# m1-output-reg.net
KiCad netlist of a schematic drawn in EAGLE
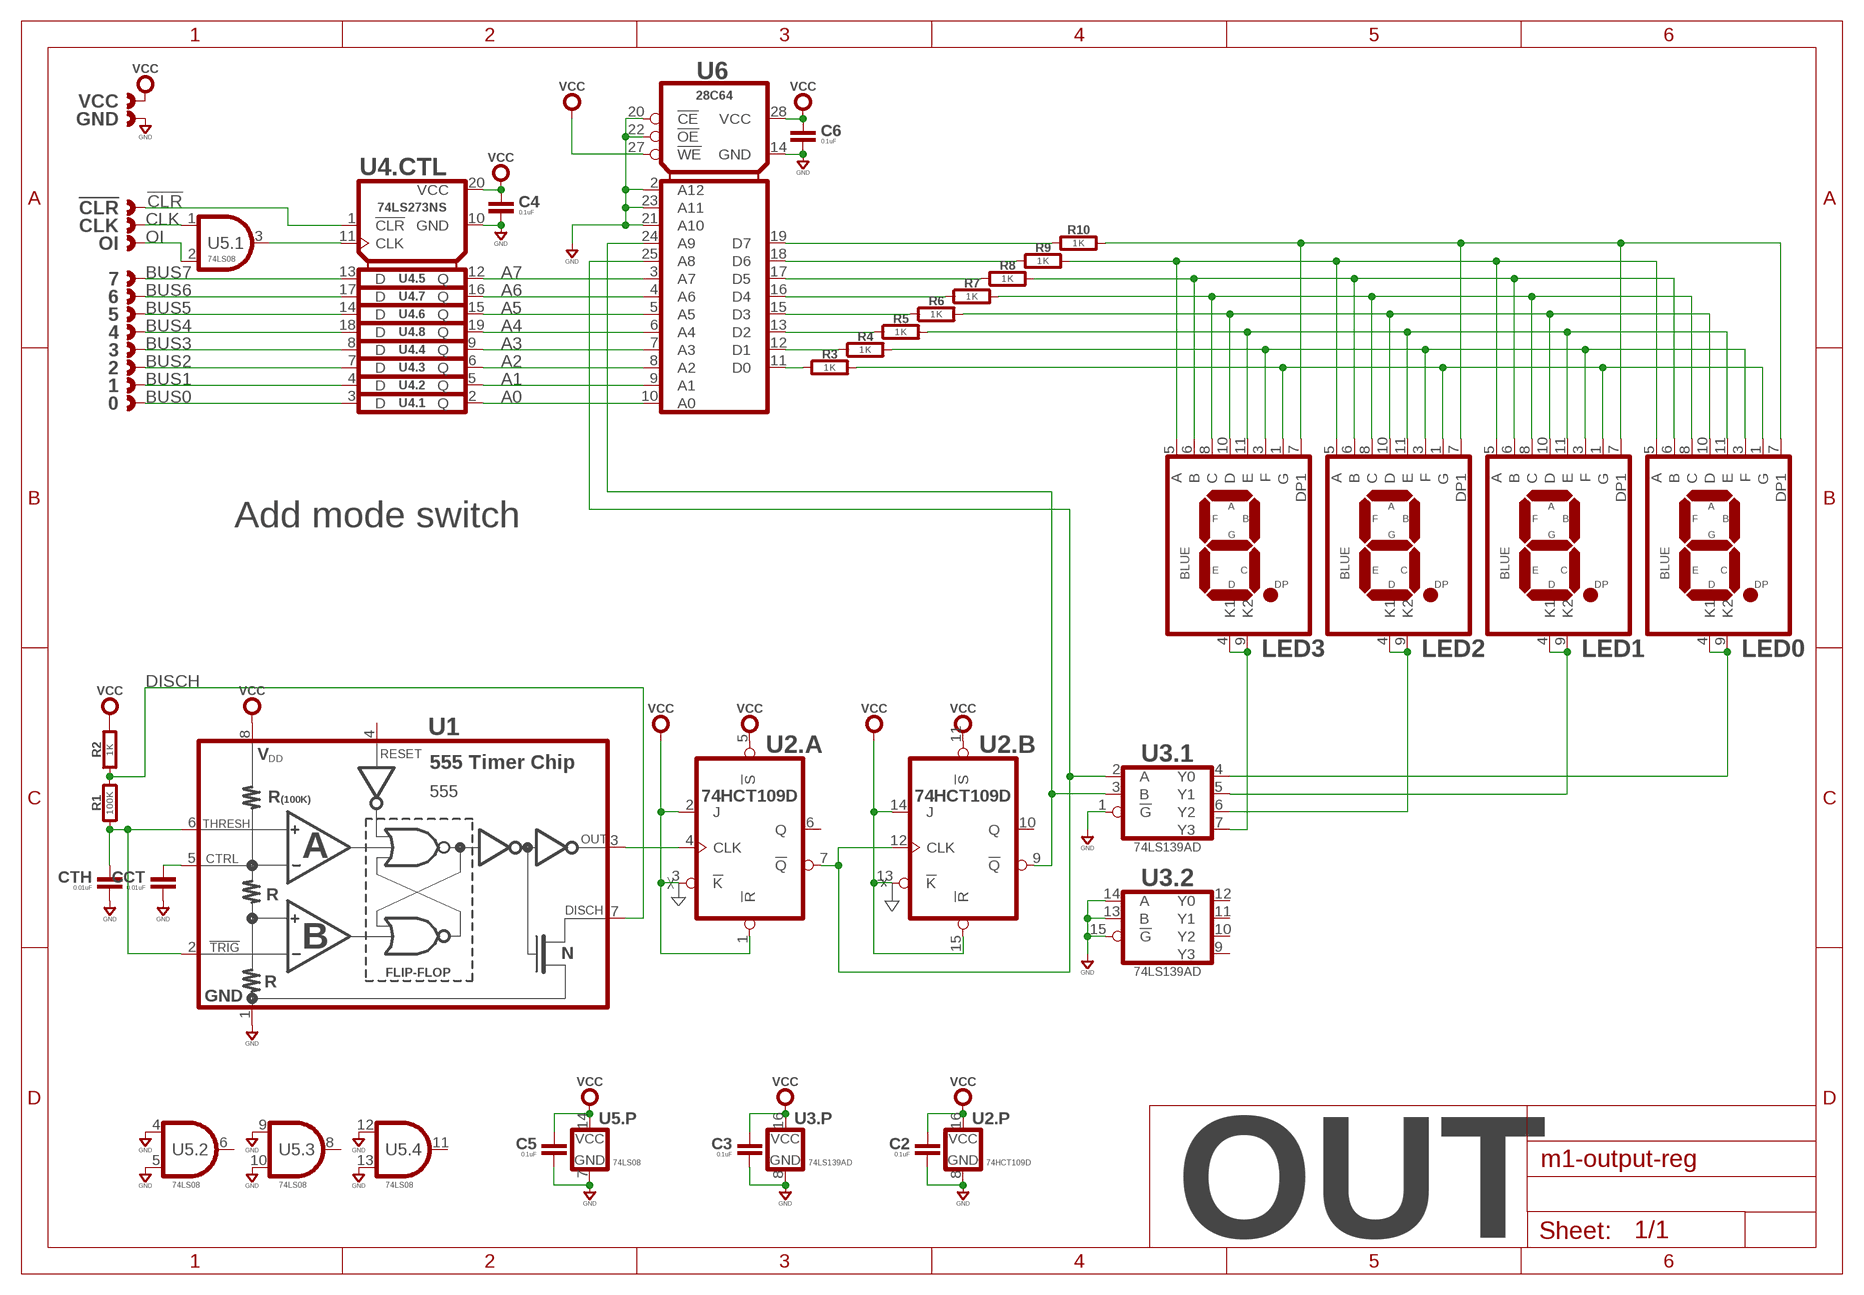
[diagram p0: schematic, sheet 1]

(export (version "E")
  (design (tool "Eeschema 10.0.6"))
  (components
    (comp (ref "!CLR")
      (value "CAST-01X1")
      (footprint "eagle-import:CAST01-2.54MM")
      (libsource (lib "eagle-import") (part "CAST-01X1"))
    )
    (comp (ref "0")
      (value "CAST-01X1")
      (footprint "eagle-import:CAST01-2.54MM")
      (libsource (lib "eagle-import") (part "CAST-01X1"))
    )
    (comp (ref "1")
      (value "CAST-01X1")
      (footprint "eagle-import:CAST01-2.54MM")
      (libsource (lib "eagle-import") (part "CAST-01X1"))
    )
    (comp (ref "2")
      (value "CAST-01X1")
      (footprint "eagle-import:CAST01-2.54MM")
      (libsource (lib "eagle-import") (part "CAST-01X1"))
    )
    (comp (ref "3")
      (value "CAST-01X1")
      (footprint "eagle-import:CAST01-2.54MM")
      (libsource (lib "eagle-import") (part "CAST-01X1"))
    )
    (comp (ref "4")
      (value "CAST-01X1")
      (footprint "eagle-import:CAST01-2.54MM")
      (libsource (lib "eagle-import") (part "CAST-01X1"))
    )
    (comp (ref "5")
      (value "CAST-01X1")
      (footprint "eagle-import:CAST01-2.54MM")
      (libsource (lib "eagle-import") (part "CAST-01X1"))
    )
    (comp (ref "6")
      (value "CAST-01X1")
      (footprint "eagle-import:CAST01-2.54MM")
      (libsource (lib "eagle-import") (part "CAST-01X1"))
    )
    (comp (ref "7")
      (value "CAST-01X1")
      (footprint "eagle-import:CAST01-2.54MM")
      (libsource (lib "eagle-import") (part "CAST-01X1"))
    )
    (comp (ref "C2")
      (value "0.1uF")
      (footprint "eagle-import:0603-CAP")
      (libsource (lib "eagle-import") (part "CAPACITOR0603"))
    )
    (comp (ref "C3")
      (value "0.1uF")
      (footprint "eagle-import:0603-CAP")
      (libsource (lib "eagle-import") (part "CAPACITOR0603"))
    )
    (comp (ref "C4")
      (value "0.1uF")
      (footprint "eagle-import:0603-CAP")
      (libsource (lib "eagle-import") (part "CAPACITOR0603"))
    )
    (comp (ref "C5")
      (value "0.1uF")
      (footprint "eagle-import:0603-CAP")
      (libsource (lib "eagle-import") (part "CAPACITOR0603"))
    )
    (comp (ref "C6")
      (value "0.1uF")
      (footprint "eagle-import:0603-CAP")
      (libsource (lib "eagle-import") (part "CAPACITOR0603"))
    )
    (comp (ref "CCT")
      (value "0.01uF")
      (footprint "eagle-import:0603-CAP")
      (libsource (lib "eagle-import") (part "CAPACITOR0603"))
    )
    (comp (ref "CLK")
      (value "CAST-01X1")
      (footprint "eagle-import:CAST01-2.54MM")
      (libsource (lib "eagle-import") (part "CAST-01X1"))
    )
    (comp (ref "CTH")
      (value "0.01uF")
      (footprint "eagle-import:0603-CAP")
      (libsource (lib "eagle-import") (part "CAPACITOR0603"))
    )
    (comp (ref "GND")
      (value "CAST-01X1")
      (footprint "eagle-import:CAST01-2.54MM")
      (libsource (lib "eagle-import") (part "CAST-01X1"))
    )
    (comp (ref "LED0")
      (value "BLUE")
      (footprint "eagle-import:AVAGO-HDSM-281B-7SEG")
      (fields (field (name "MFR") "Avago") (field (name "MPN") "HDSM-283B"))
      (libsource (lib "eagle-import") (part "SEVEN_SEG_DISP_DP028-BLUE"))
    )
    (comp (ref "LED1")
      (value "BLUE")
      (footprint "eagle-import:AVAGO-HDSM-281B-7SEG")
      (fields (field (name "MFR") "Avago") (field (name "MPN") "HDSM-283B"))
      (libsource (lib "eagle-import") (part "SEVEN_SEG_DISP_DP028-BLUE"))
    )
    (comp (ref "LED2")
      (value "BLUE")
      (footprint "eagle-import:AVAGO-HDSM-281B-7SEG")
      (fields (field (name "MFR") "Avago") (field (name "MPN") "HDSM-283B"))
      (libsource (lib "eagle-import") (part "SEVEN_SEG_DISP_DP028-BLUE"))
    )
    (comp (ref "LED3")
      (value "BLUE")
      (footprint "eagle-import:AVAGO-HDSM-281B-7SEG")
      (fields (field (name "MFR") "Avago") (field (name "MPN") "HDSM-283B"))
      (libsource (lib "eagle-import") (part "SEVEN_SEG_DISP_DP028-BLUE"))
    )
    (comp (ref "OI")
      (value "CAST-01X1")
      (footprint "eagle-import:CAST01-2.54MM")
      (libsource (lib "eagle-import") (part "CAST-01X1"))
    )
    (comp (ref "R1")
      (value "100K")
      (footprint "eagle-import:0603-RES")
      (libsource (lib "eagle-import") (part "RESISTOR0603"))
    )
    (comp (ref "R2")
      (value "1K")
      (footprint "eagle-import:0603-RES")
      (libsource (lib "eagle-import") (part "RESISTOR0603"))
    )
    (comp (ref "R3")
      (value "1K")
      (footprint "eagle-import:0603-RES")
      (libsource (lib "eagle-import") (part "RESISTOR0603"))
    )
    (comp (ref "R4")
      (value "1K")
      (footprint "eagle-import:0603-RES")
      (libsource (lib "eagle-import") (part "RESISTOR0603"))
    )
    (comp (ref "R5")
      (value "1K")
      (footprint "eagle-import:0603-RES")
      (libsource (lib "eagle-import") (part "RESISTOR0603"))
    )
    (comp (ref "R6")
      (value "1K")
      (footprint "eagle-import:0603-RES")
      (libsource (lib "eagle-import") (part "RESISTOR0603"))
    )
    (comp (ref "R7")
      (value "1K")
      (footprint "eagle-import:0603-RES")
      (libsource (lib "eagle-import") (part "RESISTOR0603"))
    )
    (comp (ref "R8")
      (value "1K")
      (footprint "eagle-import:0603-RES")
      (libsource (lib "eagle-import") (part "RESISTOR0603"))
    )
    (comp (ref "R9")
      (value "1K")
      (footprint "eagle-import:0603-RES")
      (libsource (lib "eagle-import") (part "RESISTOR0603"))
    )
    (comp (ref "R10")
      (value "1K")
      (footprint "eagle-import:0603-RES")
      (libsource (lib "eagle-import") (part "RESISTOR0603"))
    )
    (comp (ref "U1")
      (value "555")
      (footprint "eagle-import:SOP08")
      (fields (field (name "MFR") "TI") (field (name "MPN") "NE555PSR"))
      (libsource (lib "eagle-import") (part "555SOIC"))
    )
    (comp (ref "U2")
      (value "74HCT109D")
      (footprint "eagle-import:SO16")
      (libsource (lib "eagle-import") (part "74109?DAHCT"))
    )
    (comp (ref "U3")
      (value "74LS139AD")
      (footprint "eagle-import:SO16")
      (libsource (lib "eagle-import") (part "74139?DLS"))
    )
    (comp (ref "U4")
      (value "74LS273NS")
      (footprint "eagle-import:SO20")
      (libsource (lib "eagle-import") (part "74273?NSLS"))
    )
    (comp (ref "U5")
      (value "74LS08")
      (footprint "eagle-import:SOP14")
      (fields (field (name "MPN") "74LS08D"))
      (libsource (lib "eagle-import") (part "7408?DLS"))
    )
    (comp (ref "U6")
      (value "28C64")
      (footprint "eagle-import:SO28")
      (fields (field (name "MFR") "Microchip") (field (name "MPN") "AT28C64B-15SU"))
      (libsource (lib "eagle-import") (part "2864?SC"))
    )
    (comp (ref "VCC")
      (value "CAST-01X1")
      (footprint "eagle-import:CAST01-2.54MM")
      (libsource (lib "eagle-import") (part "CAST-01X1"))
    )
  )
  (nets
    (net (code "1") (name "/A0") (class "Default")
      (node (ref "U4") (pin "2") (pinfunction "Q_2") (pintype "output"))
      (node (ref "U6") (pin "10") (pinfunction "A0_10") (pintype "input"))
    )
    (net (code "2") (name "/A1") (class "Default")
      (node (ref "U4") (pin "5") (pinfunction "Q_5") (pintype "output"))
      (node (ref "U6") (pin "9") (pinfunction "A1_9") (pintype "input"))
    )
    (net (code "3") (name "/A2") (class "Default")
      (node (ref "U4") (pin "6") (pinfunction "Q_6") (pintype "output"))
      (node (ref "U6") (pin "8") (pinfunction "A2_8") (pintype "input"))
    )
    (net (code "4") (name "/A3") (class "Default")
      (node (ref "U4") (pin "9") (pinfunction "Q_9") (pintype "output"))
      (node (ref "U6") (pin "7") (pinfunction "A3_7") (pintype "input"))
    )
    (net (code "5") (name "/A4") (class "Default")
      (node (ref "U4") (pin "19") (pinfunction "Q_19") (pintype "output"))
      (node (ref "U6") (pin "6") (pinfunction "A4_6") (pintype "input"))
    )
    (net (code "6") (name "/A5") (class "Default")
      (node (ref "U4") (pin "15") (pinfunction "Q_15") (pintype "output"))
      (node (ref "U6") (pin "5") (pinfunction "A5_5") (pintype "input"))
    )
    (net (code "7") (name "/A6") (class "Default")
      (node (ref "U4") (pin "16") (pinfunction "Q_16") (pintype "output"))
      (node (ref "U6") (pin "4") (pinfunction "A6_4") (pintype "input"))
    )
    (net (code "8") (name "/A7") (class "Default")
      (node (ref "U4") (pin "12") (pinfunction "Q_12") (pintype "output"))
      (node (ref "U6") (pin "3") (pinfunction "A7_3") (pintype "input"))
    )
    (net (code "9") (name "/BUS0") (class "Default")
      (node (ref "0") (pin "1") (pinfunction "1_1") (pintype "bidirectional"))
      (node (ref "U4") (pin "3") (pinfunction "D_3") (pintype "input"))
    )
    (net (code "10") (name "/BUS1") (class "Default")
      (node (ref "1") (pin "1") (pinfunction "1_1") (pintype "bidirectional"))
      (node (ref "U4") (pin "4") (pinfunction "D_4") (pintype "input"))
    )
    (net (code "11") (name "/BUS2") (class "Default")
      (node (ref "2") (pin "1") (pinfunction "1_1") (pintype "bidirectional"))
      (node (ref "U4") (pin "7") (pinfunction "D_7") (pintype "input"))
    )
    (net (code "12") (name "/BUS3") (class "Default")
      (node (ref "3") (pin "1") (pinfunction "1_1") (pintype "bidirectional"))
      (node (ref "U4") (pin "8") (pinfunction "D_8") (pintype "input"))
    )
    (net (code "13") (name "/BUS4") (class "Default")
      (node (ref "4") (pin "1") (pinfunction "1_1") (pintype "bidirectional"))
      (node (ref "U4") (pin "18") (pinfunction "D_18") (pintype "input"))
    )
    (net (code "14") (name "/BUS5") (class "Default")
      (node (ref "5") (pin "1") (pinfunction "1_1") (pintype "bidirectional"))
      (node (ref "U4") (pin "14") (pinfunction "D_14") (pintype "input"))
    )
    (net (code "15") (name "/BUS6") (class "Default")
      (node (ref "6") (pin "1") (pinfunction "1_1") (pintype "bidirectional"))
      (node (ref "U4") (pin "17") (pinfunction "D_17") (pintype "input"))
    )
    (net (code "16") (name "/BUS7") (class "Default")
      (node (ref "7") (pin "1") (pinfunction "1_1") (pintype "bidirectional"))
      (node (ref "U4") (pin "13") (pinfunction "D_13") (pintype "input"))
    )
    (net (code "17") (name "/CLK") (class "Default")
      (node (ref "CLK") (pin "1") (pinfunction "1_1") (pintype "bidirectional"))
      (node (ref "U5") (pin "1") (pinfunction "A_1") (pintype "input"))
    )
    (net (code "18") (name "/DISCH") (class "Default")
      (node (ref "R1") (pin "1") (pinfunction "1_1") (pintype "passive"))
      (node (ref "R2") (pin "1") (pinfunction "1_1") (pintype "passive"))
      (node (ref "U1") (pin "7") (pinfunction "DISCHARGE_7") (pintype "output"))
    )
    (net (code "19") (name "/OI") (class "Default")
      (node (ref "OI") (pin "1") (pinfunction "1_1") (pintype "bidirectional"))
      (node (ref "U5") (pin "2") (pinfunction "B_2") (pintype "input"))
    )
    (net (code "20") (name "/~{CLR}") (class "Default")
      (node (ref "!CLR") (pin "1") (pinfunction "1_1") (pintype "bidirectional"))
      (node (ref "U4") (pin "1") (pinfunction "~{CLR}_1") (pintype "input"))
    )
    (net (code "21") (name "GND") (class "Default")
      (node (ref "C2") (pin "2") (pinfunction "2_2") (pintype "passive"))
      (node (ref "C3") (pin "2") (pinfunction "2_2") (pintype "passive"))
      (node (ref "C4") (pin "2") (pinfunction "2_2") (pintype "passive"))
      (node (ref "C5") (pin "2") (pinfunction "2_2") (pintype "passive"))
      (node (ref "C6") (pin "2") (pinfunction "2_2") (pintype "passive"))
      (node (ref "CCT") (pin "2") (pinfunction "2_2") (pintype "passive"))
      (node (ref "CTH") (pin "2") (pinfunction "2_2") (pintype "passive"))
      (node (ref "GND") (pin "1") (pinfunction "1_1") (pintype "bidirectional"))
      (node (ref "U1") (pin "1") (pinfunction "GND_1") (pintype "power_in"))
      (node (ref "U2") (pin "8") (pinfunction "GND_8") (pintype "power_in"))
      (node (ref "U3") (pin "1") (pinfunction "~{G}_1") (pintype "bidirectional"))
      (node (ref "U3") (pin "13") (pinfunction "B_13") (pintype "bidirectional"))
      (node (ref "U3") (pin "14") (pinfunction "A_14") (pintype "bidirectional"))
      (node (ref "U3") (pin "15") (pinfunction "~{G}_15") (pintype "bidirectional"))
      (node (ref "U3") (pin "8") (pinfunction "GND_8") (pintype "power_in"))
      (node (ref "U4") (pin "10") (pinfunction "GND_10") (pintype "power_in"))
      (node (ref "U5") (pin "10") (pinfunction "B_10") (pintype "input"))
      (node (ref "U5") (pin "12") (pinfunction "A_12") (pintype "input"))
      (node (ref "U5") (pin "13") (pinfunction "B_13") (pintype "input"))
      (node (ref "U5") (pin "4") (pinfunction "A_4") (pintype "input"))
      (node (ref "U5") (pin "5") (pinfunction "B_5") (pintype "input"))
      (node (ref "U5") (pin "7") (pinfunction "GND_7") (pintype "power_in"))
      (node (ref "U5") (pin "9") (pinfunction "A_9") (pintype "input"))
      (node (ref "U6") (pin "14") (pinfunction "GND_14") (pintype "power_in"))
      (node (ref "U6") (pin "2") (pinfunction "A12_2") (pintype "input"))
      (node (ref "U6") (pin "20") (pinfunction "~{CE}_20") (pintype "input"))
      (node (ref "U6") (pin "21") (pinfunction "A10_21") (pintype "input"))
      (node (ref "U6") (pin "22") (pinfunction "~{OE}_22") (pintype "input"))
      (node (ref "U6") (pin "23") (pinfunction "A11_23") (pintype "input"))
    )
    (net (code "22") (name "Net-(LED0-A)") (class "Default")
      (node (ref "LED0") (pin "5") (pinfunction "A_5") (pintype "bidirectional"))
      (node (ref "LED1") (pin "5") (pinfunction "A_5") (pintype "bidirectional"))
      (node (ref "LED2") (pin "5") (pinfunction "A_5") (pintype "bidirectional"))
      (node (ref "LED3") (pin "5") (pinfunction "A_5") (pintype "bidirectional"))
      (node (ref "R9") (pin "2") (pinfunction "2_2") (pintype "passive"))
    )
    (net (code "23") (name "Net-(LED0-B)") (class "Default")
      (node (ref "LED0") (pin "6") (pinfunction "B_6") (pintype "bidirectional"))
      (node (ref "LED1") (pin "6") (pinfunction "B_6") (pintype "bidirectional"))
      (node (ref "LED2") (pin "6") (pinfunction "B_6") (pintype "bidirectional"))
      (node (ref "LED3") (pin "6") (pinfunction "B_6") (pintype "bidirectional"))
      (node (ref "R8") (pin "2") (pinfunction "2_2") (pintype "passive"))
    )
    (net (code "24") (name "Net-(LED0-C)") (class "Default")
      (node (ref "LED0") (pin "8") (pinfunction "C_8") (pintype "bidirectional"))
      (node (ref "LED1") (pin "8") (pinfunction "C_8") (pintype "bidirectional"))
      (node (ref "LED2") (pin "8") (pinfunction "C_8") (pintype "bidirectional"))
      (node (ref "LED3") (pin "8") (pinfunction "C_8") (pintype "bidirectional"))
      (node (ref "R7") (pin "2") (pinfunction "2_2") (pintype "passive"))
    )
    (net (code "25") (name "Net-(LED0-D)") (class "Default")
      (node (ref "LED0") (pin "10") (pinfunction "D_10") (pintype "bidirectional"))
      (node (ref "LED1") (pin "10") (pinfunction "D_10") (pintype "bidirectional"))
      (node (ref "LED2") (pin "10") (pinfunction "D_10") (pintype "bidirectional"))
      (node (ref "LED3") (pin "10") (pinfunction "D_10") (pintype "bidirectional"))
      (node (ref "R6") (pin "2") (pinfunction "2_2") (pintype "passive"))
    )
    (net (code "26") (name "Net-(LED0-DP1)") (class "Default")
      (node (ref "LED0") (pin "7") (pinfunction "DP1_7") (pintype "bidirectional"))
      (node (ref "LED1") (pin "7") (pinfunction "DP1_7") (pintype "bidirectional"))
      (node (ref "LED2") (pin "7") (pinfunction "DP1_7") (pintype "bidirectional"))
      (node (ref "LED3") (pin "7") (pinfunction "DP1_7") (pintype "bidirectional"))
      (node (ref "R10") (pin "2") (pinfunction "2_2") (pintype "passive"))
    )
    (net (code "27") (name "Net-(LED0-E)") (class "Default")
      (node (ref "LED0") (pin "11") (pinfunction "E_11") (pintype "bidirectional"))
      (node (ref "LED1") (pin "11") (pinfunction "E_11") (pintype "bidirectional"))
      (node (ref "LED2") (pin "11") (pinfunction "E_11") (pintype "bidirectional"))
      (node (ref "LED3") (pin "11") (pinfunction "E_11") (pintype "bidirectional"))
      (node (ref "R5") (pin "2") (pinfunction "2_2") (pintype "passive"))
    )
    (net (code "28") (name "Net-(LED0-F)") (class "Default")
      (node (ref "LED0") (pin "3") (pinfunction "F_3") (pintype "bidirectional"))
      (node (ref "LED1") (pin "3") (pinfunction "F_3") (pintype "bidirectional"))
      (node (ref "LED2") (pin "3") (pinfunction "F_3") (pintype "bidirectional"))
      (node (ref "LED3") (pin "3") (pinfunction "F_3") (pintype "bidirectional"))
      (node (ref "R4") (pin "2") (pinfunction "2_2") (pintype "passive"))
    )
    (net (code "29") (name "Net-(LED0-G)") (class "Default")
      (node (ref "LED0") (pin "1") (pinfunction "G_1") (pintype "bidirectional"))
      (node (ref "LED1") (pin "1") (pinfunction "G_1") (pintype "bidirectional"))
      (node (ref "LED2") (pin "1") (pinfunction "G_1") (pintype "bidirectional"))
      (node (ref "LED3") (pin "1") (pinfunction "G_1") (pintype "bidirectional"))
      (node (ref "R3") (pin "2") (pinfunction "2_2") (pintype "passive"))
    )
    (net (code "30") (name "Net-(LED0-K1)") (class "Default")
      (node (ref "LED0") (pin "4") (pinfunction "K1_4") (pintype "bidirectional"))
      (node (ref "LED0") (pin "9") (pinfunction "K2_9") (pintype "bidirectional"))
      (node (ref "U3") (pin "4") (pinfunction "Y0_4") (pintype "bidirectional"))
    )
    (net (code "31") (name "Net-(LED1-K1)") (class "Default")
      (node (ref "LED1") (pin "4") (pinfunction "K1_4") (pintype "bidirectional"))
      (node (ref "LED1") (pin "9") (pinfunction "K2_9") (pintype "bidirectional"))
      (node (ref "U3") (pin "5") (pinfunction "Y1_5") (pintype "bidirectional"))
    )
    (net (code "32") (name "Net-(LED2-K1)") (class "Default")
      (node (ref "LED2") (pin "4") (pinfunction "K1_4") (pintype "bidirectional"))
      (node (ref "LED2") (pin "9") (pinfunction "K2_9") (pintype "bidirectional"))
      (node (ref "U3") (pin "6") (pinfunction "Y2_6") (pintype "bidirectional"))
    )
    (net (code "33") (name "Net-(LED3-K1)") (class "Default")
      (node (ref "LED3") (pin "4") (pinfunction "K1_4") (pintype "bidirectional"))
      (node (ref "LED3") (pin "9") (pinfunction "K2_9") (pintype "bidirectional"))
      (node (ref "U3") (pin "7") (pinfunction "Y3_7") (pintype "bidirectional"))
    )
    (net (code "34") (name "Net-(U1-CONTROL)") (class "Default")
      (node (ref "CCT") (pin "1") (pinfunction "1_1") (pintype "passive"))
      (node (ref "U1") (pin "5") (pinfunction "CONTROL_5") (pintype "input"))
    )
    (net (code "35") (name "Net-(U1-OUTPUT)") (class "Default")
      (node (ref "U1") (pin "3") (pinfunction "OUTPUT_3") (pintype "output"))
      (node (ref "U2") (pin "4") (pinfunction "CLK_4") (pintype "input"))
    )
    (net (code "36") (name "Net-(U1-THRESHOLD)") (class "Default")
      (node (ref "CTH") (pin "1") (pinfunction "1_1") (pintype "passive"))
      (node (ref "R1") (pin "2") (pinfunction "2_2") (pintype "passive"))
      (node (ref "U1") (pin "2") (pinfunction "TRIGGER#_2") (pintype "input"))
      (node (ref "U1") (pin "6") (pinfunction "THRESHOLD_6") (pintype "input"))
    )
    (net (code "37") (name "Net-(U2A-~{Q})") (class "Default")
      (node (ref "U2") (pin "12") (pinfunction "CLK_12") (pintype "input"))
      (node (ref "U2") (pin "7") (pinfunction "~{Q}_7") (pintype "output"))
      (node (ref "U3") (pin "2") (pinfunction "A_2") (pintype "bidirectional"))
      (node (ref "U6") (pin "25") (pinfunction "A8_25") (pintype "input"))
    )
    (net (code "38") (name "Net-(U2B-~{Q})") (class "Default")
      (node (ref "U2") (pin "9") (pinfunction "~{Q}_9") (pintype "output"))
      (node (ref "U3") (pin "3") (pinfunction "B_3") (pintype "bidirectional"))
      (node (ref "U6") (pin "24") (pinfunction "A9_24") (pintype "input"))
    )
    (net (code "39") (name "Net-(U4I-CLK)") (class "Default")
      (node (ref "U4") (pin "11") (pinfunction "CLK_11") (pintype "input"))
      (node (ref "U5") (pin "3") (pinfunction "Y_3") (pintype "output"))
    )
    (net (code "40") (name "Net-(U6-D0)") (class "Default")
      (node (ref "R3") (pin "1") (pinfunction "1_1") (pintype "passive"))
      (node (ref "U6") (pin "11") (pinfunction "D0_11") (pintype "bidirectional"))
    )
    (net (code "41") (name "Net-(U6-D1)") (class "Default")
      (node (ref "R4") (pin "1") (pinfunction "1_1") (pintype "passive"))
      (node (ref "U6") (pin "12") (pinfunction "D1_12") (pintype "bidirectional"))
    )
    (net (code "42") (name "Net-(U6-D2)") (class "Default")
      (node (ref "R5") (pin "1") (pinfunction "1_1") (pintype "passive"))
      (node (ref "U6") (pin "13") (pinfunction "D2_13") (pintype "bidirectional"))
    )
    (net (code "43") (name "Net-(U6-D3)") (class "Default")
      (node (ref "R6") (pin "1") (pinfunction "1_1") (pintype "passive"))
      (node (ref "U6") (pin "15") (pinfunction "D3_15") (pintype "bidirectional"))
    )
    (net (code "44") (name "Net-(U6-D4)") (class "Default")
      (node (ref "R7") (pin "1") (pinfunction "1_1") (pintype "passive"))
      (node (ref "U6") (pin "16") (pinfunction "D4_16") (pintype "bidirectional"))
    )
    (net (code "45") (name "Net-(U6-D5)") (class "Default")
      (node (ref "R8") (pin "1") (pinfunction "1_1") (pintype "passive"))
      (node (ref "U6") (pin "17") (pinfunction "D5_17") (pintype "bidirectional"))
    )
    (net (code "46") (name "Net-(U6-D6)") (class "Default")
      (node (ref "R9") (pin "1") (pinfunction "1_1") (pintype "passive"))
      (node (ref "U6") (pin "18") (pinfunction "D6_18") (pintype "bidirectional"))
    )
    (net (code "47") (name "Net-(U6-D7)") (class "Default")
      (node (ref "R10") (pin "1") (pinfunction "1_1") (pintype "passive"))
      (node (ref "U6") (pin "19") (pinfunction "D7_19") (pintype "bidirectional"))
    )
    (net (code "48") (name "VCC") (class "Default")
      (node (ref "C2") (pin "1") (pinfunction "1_1") (pintype "passive"))
      (node (ref "C3") (pin "1") (pinfunction "1_1") (pintype "passive"))
      (node (ref "C4") (pin "1") (pinfunction "1_1") (pintype "passive"))
      (node (ref "C5") (pin "1") (pinfunction "1_1") (pintype "passive"))
      (node (ref "C6") (pin "1") (pinfunction "1_1") (pintype "passive"))
      (node (ref "R2") (pin "2") (pinfunction "2_2") (pintype "passive"))
      (node (ref "U1") (pin "8") (pinfunction "VDD_8") (pintype "power_in"))
      (node (ref "U2") (pin "1") (pinfunction "~{R}_1") (pintype "input"))
      (node (ref "U2") (pin "11") (pinfunction "~{S}_11") (pintype "input"))
      (node (ref "U2") (pin "13") (pinfunction "~{K}_13") (pintype "input"))
      (node (ref "U2") (pin "14") (pinfunction "J_14") (pintype "input"))
      (node (ref "U2") (pin "15") (pinfunction "~{R}_15") (pintype "input"))
      (node (ref "U2") (pin "16") (pinfunction "VCC_16") (pintype "power_in"))
      (node (ref "U2") (pin "2") (pinfunction "J_2") (pintype "input"))
      (node (ref "U2") (pin "3") (pinfunction "~{K}_3") (pintype "input"))
      (node (ref "U2") (pin "5") (pinfunction "~{S}_5") (pintype "input"))
      (node (ref "U3") (pin "16") (pinfunction "VCC_16") (pintype "power_in"))
      (node (ref "U4") (pin "20") (pinfunction "VCC_20") (pintype "power_in"))
      (node (ref "U5") (pin "14") (pinfunction "VCC_14") (pintype "power_in"))
      (node (ref "U6") (pin "27") (pinfunction "~{WE}_27") (pintype "input"))
      (node (ref "U6") (pin "28") (pinfunction "VCC_28") (pintype "power_in"))
      (node (ref "VCC") (pin "1") (pinfunction "1_1") (pintype "bidirectional"))
    )
    (net (code "49") (name "unconnected-(U1-RESET#-Pad4)") (class "Default")
      (node (ref "U1") (pin "4") (pinfunction "RESET#_4") (pintype "bidirectional"))
    )
    (net (code "50") (name "unconnected-(U2A-Q-Pad6)") (class "Default")
      (node (ref "U2") (pin "6") (pinfunction "Q_6") (pintype "output"))
    )
    (net (code "51") (name "unconnected-(U2B-Q-Pad10)") (class "Default")
      (node (ref "U2") (pin "10") (pinfunction "Q_10") (pintype "output"))
    )
    (net (code "52") (name "unconnected-(U3B-Y0-Pad12)") (class "Default")
      (node (ref "U3") (pin "12") (pinfunction "Y0_12") (pintype "bidirectional"))
    )
    (net (code "53") (name "unconnected-(U3B-Y1-Pad11)") (class "Default")
      (node (ref "U3") (pin "11") (pinfunction "Y1_11") (pintype "bidirectional"))
    )
    (net (code "54") (name "unconnected-(U3B-Y2-Pad10)") (class "Default")
      (node (ref "U3") (pin "10") (pinfunction "Y2_10") (pintype "bidirectional"))
    )
    (net (code "55") (name "unconnected-(U3B-Y3-Pad9)") (class "Default")
      (node (ref "U3") (pin "9") (pinfunction "Y3_9") (pintype "bidirectional"))
    )
    (net (code "56") (name "unconnected-(U5B-Y-Pad6)") (class "Default")
      (node (ref "U5") (pin "6") (pinfunction "Y_6") (pintype "output"))
    )
    (net (code "57") (name "unconnected-(U5C-Y-Pad8)") (class "Default")
      (node (ref "U5") (pin "8") (pinfunction "Y_8") (pintype "output"))
    )
    (net (code "58") (name "unconnected-(U5D-Y-Pad11)") (class "Default")
      (node (ref "U5") (pin "11") (pinfunction "Y_11") (pintype "output"))
    )
  )
)
